# Top_level.net
KiCad netlist of a schematic drawn in Altium Designer
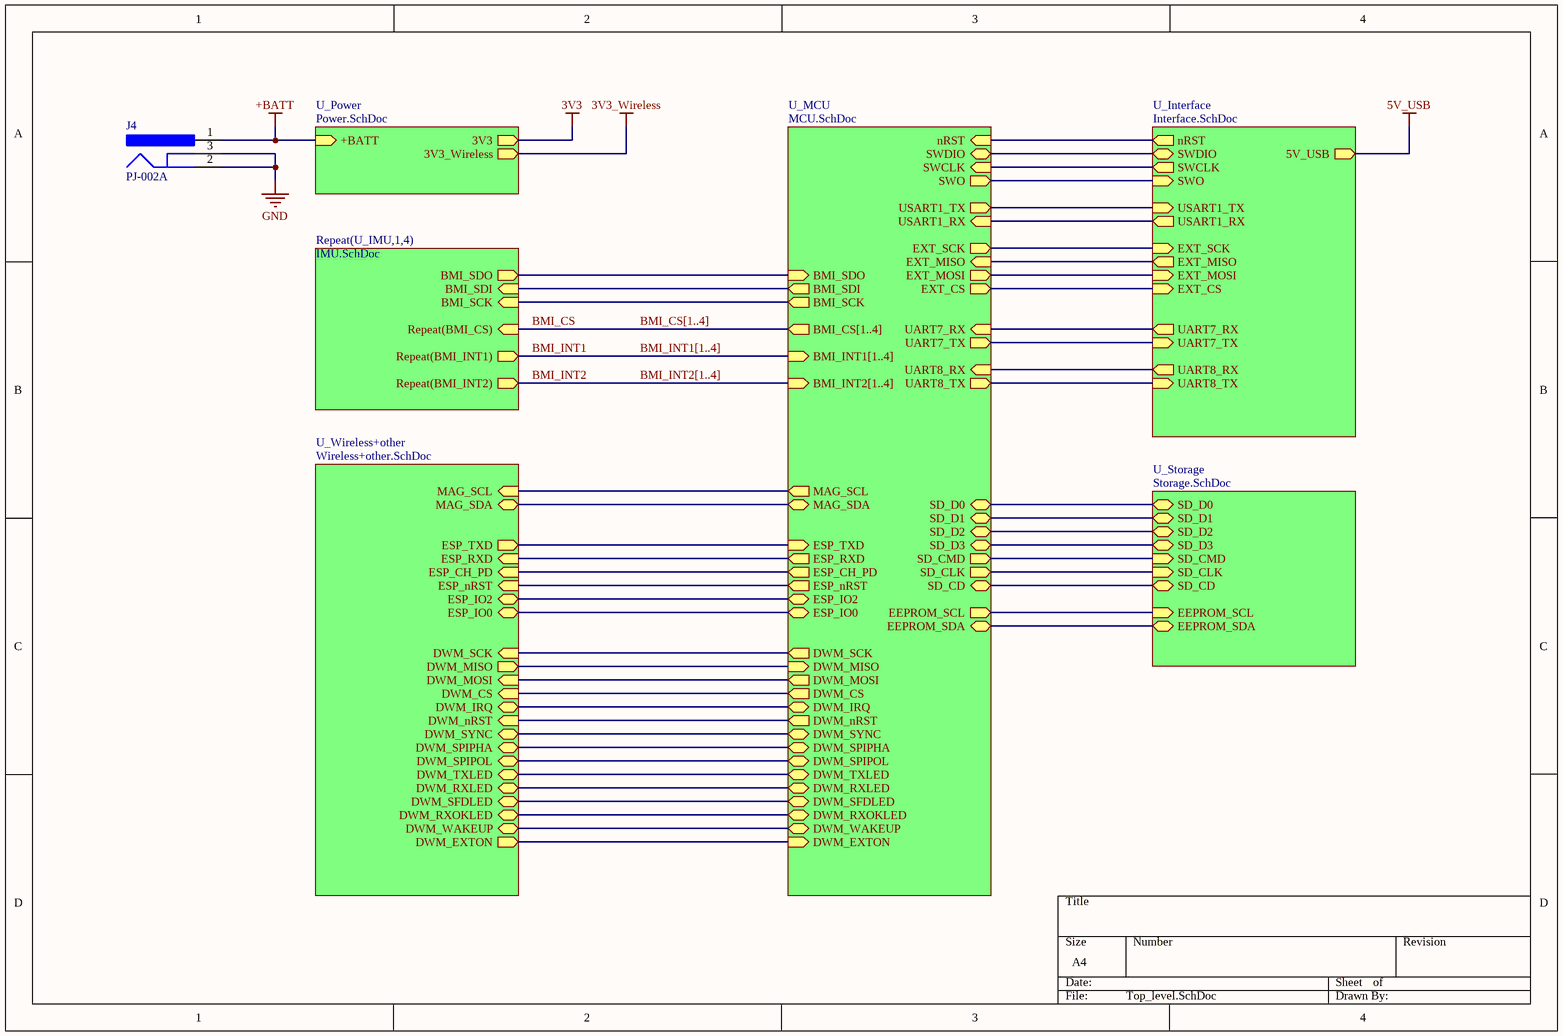
[diagram p0: Top_level.SchDoc]

(export (version "E")
  (design (tool "Eeschema 10.0.6"))
  (components
    (comp (ref "J4")
      (value "PJ-002A")
      (footprint "CUI-PJ-002A_V")
      (fields (field (name "MANUFACTURER") "CUIInc."))
      (libsource (lib "Altium Content Vault") (part "JACK-2CD3-RN_B"))
    )
  )
  (nets
    (net (code "13") (name "+BATT") (class "Default")
      (node (ref "J4") (pin "1") (pinfunction "1_1") (pintype "passive"))
    )
    (net (code "72") (name "GND") (class "Default")
      (node (ref "J4") (pin "2") (pinfunction "2_2") (pintype "passive"))
      (node (ref "J4") (pin "3") (pinfunction "3_3") (pintype "passive"))
    )
  )
)
